# Moteino.net
KiCad netlist of a schematic drawn in EAGLE
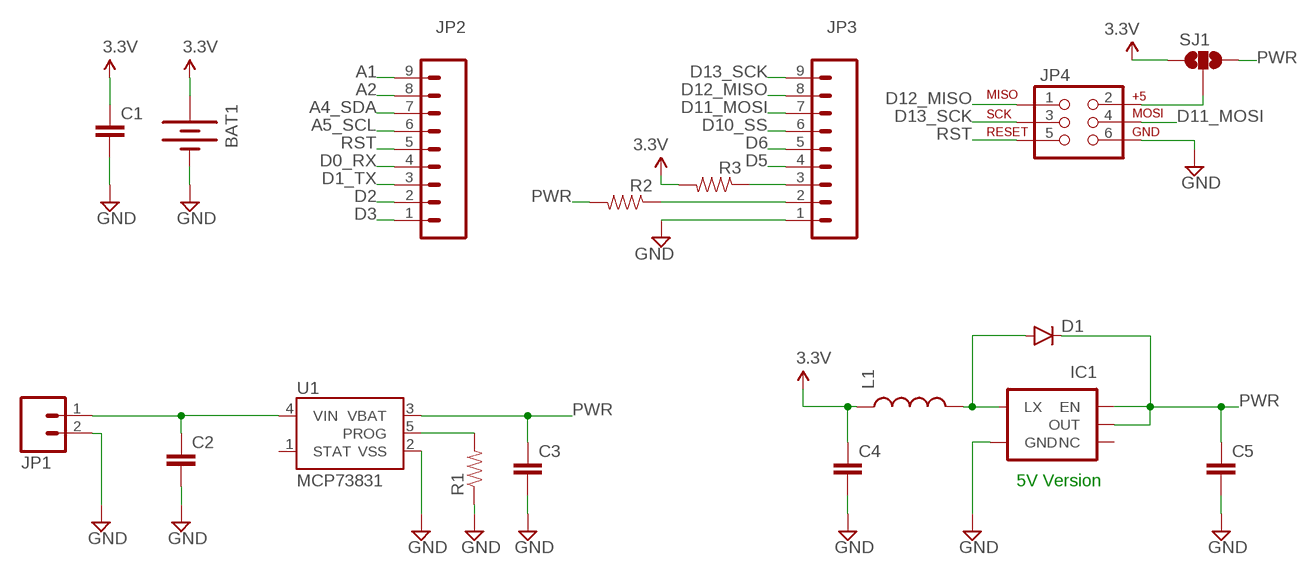
[diagram p0: schematic, sheet 1]

(export (version "E")
  (design (tool "Eeschema 10.0.6"))
  (components
    (comp (ref "BAT1")
      (value "BATTERY12MM")
      (footprint "eagle-import:BATTCON_12MM")
      (libsource (lib "eagle-import") (part "BATTERY12MM"))
    )
    (comp (ref "C1")
      (value "CAP0603-CAP")
      (footprint "eagle-import:0603-CAP")
      (libsource (lib "eagle-import") (part "CAP0603-CAP"))
    )
    (comp (ref "C2")
      (value "CAP0603-CAP")
      (footprint "eagle-import:0603-CAP")
      (libsource (lib "eagle-import") (part "CAP0603-CAP"))
    )
    (comp (ref "C3")
      (value "CAP0603-CAP")
      (footprint "eagle-import:0603-CAP")
      (libsource (lib "eagle-import") (part "CAP0603-CAP"))
    )
    (comp (ref "C4")
      (value "CAP0603-CAP")
      (footprint "eagle-import:0603-CAP")
      (libsource (lib "eagle-import") (part "CAP0603-CAP"))
    )
    (comp (ref "C5")
      (value "CAP0603-CAP")
      (footprint "eagle-import:0603-CAP")
      (libsource (lib "eagle-import") (part "CAP0603-CAP"))
    )
    (comp (ref "D1")
      (value "DIODESMA")
      (footprint "eagle-import:SMA-DIODE")
      (libsource (lib "eagle-import") (part "DIODESMA"))
    )
    (comp (ref "IC1")
      (value "V_REG_NCP1400SOT23-5")
      (footprint "eagle-import:SOT23-5")
      (libsource (lib "eagle-import") (part "V_REG_NCP1400SOT23-5"))
    )
    (comp (ref "JP1")
      (value "M02PTH")
      (footprint "eagle-import:1X02")
      (libsource (lib "eagle-import") (part "M02PTH"))
    )
    (comp (ref "JP2")
      (value "M09")
      (footprint "eagle-import:1X09")
      (libsource (lib "eagle-import") (part "M09"))
    )
    (comp (ref "JP3")
      (value "M09")
      (footprint "eagle-import:1X09")
      (libsource (lib "eagle-import") (part "M09"))
    )
    (comp (ref "JP4")
      (value "AVR_SPI_PRG_6TESTPOINTS")
      (footprint "eagle-import:2X3_TEST_POINTS")
      (libsource (lib "eagle-import") (part "AVR_SPI_PRG_6TESTPOINTS"))
    )
    (comp (ref "L1")
      (value "INDUCTORINDUCTOR_4.7UH")
      (footprint "eagle-import:INDUCTOR_4.7UH")
      (libsource (lib "eagle-import") (part "INDUCTORINDUCTOR_4.7UH"))
    )
    (comp (ref "R1")
      (value "RESISTOR0603-RES")
      (footprint "eagle-import:0603-RES")
      (libsource (lib "eagle-import") (part "RESISTOR0603-RES"))
    )
    (comp (ref "R2")
      (value "RESISTOR0603-RES")
      (footprint "eagle-import:0603-RES")
      (libsource (lib "eagle-import") (part "RESISTOR0603-RES"))
    )
    (comp (ref "R3")
      (value "RESISTOR0603-RES")
      (footprint "eagle-import:0603-RES")
      (libsource (lib "eagle-import") (part "RESISTOR0603-RES"))
    )
    (comp (ref "SJ1")
      (value "JUMPER-PAD-3-NOFULL_BOX_SILK")
      (footprint "eagle-import:PAD-JUMPER-3-NO_YES_SILK_FULL_BOX")
      (libsource (lib "eagle-import") (part "JUMPER-PAD-3-NOFULL_BOX_SILK"))
    )
    (comp (ref "U1")
      (value "MCP73831")
      (footprint "eagle-import:SOT23-5")
      (libsource (lib "eagle-import") (part "MCP73831"))
    )
  )
  (nets
    (net (code "1") (name "/A1") (class "Default")
      (node (ref "JP2") (pin "9") (pinfunction "9_9") (pintype "passive"))
    )
    (net (code "2") (name "/A2") (class "Default")
      (node (ref "JP2") (pin "8") (pinfunction "8_8") (pintype "passive"))
    )
    (net (code "3") (name "/A4_SDA") (class "Default")
      (node (ref "JP2") (pin "7") (pinfunction "7_7") (pintype "passive"))
    )
    (net (code "4") (name "/A5_SCL") (class "Default")
      (node (ref "JP2") (pin "6") (pinfunction "6_6") (pintype "passive"))
    )
    (net (code "5") (name "/D0_RX") (class "Default")
      (node (ref "JP2") (pin "4") (pinfunction "4_4") (pintype "passive"))
    )
    (net (code "6") (name "/D1_TX") (class "Default")
      (node (ref "JP2") (pin "3") (pinfunction "3_3") (pintype "passive"))
    )
    (net (code "7") (name "/D2") (class "Default")
      (node (ref "JP2") (pin "2") (pinfunction "2_2") (pintype "passive"))
    )
    (net (code "8") (name "/D3") (class "Default")
      (node (ref "JP2") (pin "1") (pinfunction "1_1") (pintype "passive"))
    )
    (net (code "9") (name "/D5") (class "Default")
      (node (ref "JP3") (pin "4") (pinfunction "4_4") (pintype "passive"))
    )
    (net (code "10") (name "/D6") (class "Default")
      (node (ref "JP3") (pin "5") (pinfunction "5_5") (pintype "passive"))
    )
    (net (code "11") (name "/D10_SS") (class "Default")
      (node (ref "JP3") (pin "6") (pinfunction "6_6") (pintype "passive"))
    )
    (net (code "12") (name "/D11_MOSI") (class "Default")
      (node (ref "JP3") (pin "7") (pinfunction "7_7") (pintype "passive"))
      (node (ref "JP4") (pin "4") (pinfunction "4_4") (pintype "passive"))
    )
    (net (code "13") (name "/D12_MISO") (class "Default")
      (node (ref "JP3") (pin "8") (pinfunction "8_8") (pintype "passive"))
      (node (ref "JP4") (pin "1") (pinfunction "1_1") (pintype "passive"))
    )
    (net (code "14") (name "/D13_SCK") (class "Default")
      (node (ref "JP3") (pin "9") (pinfunction "9_9") (pintype "passive"))
      (node (ref "JP4") (pin "3") (pinfunction "3_3") (pintype "passive"))
    )
    (net (code "15") (name "/PWR") (class "Default")
      (node (ref "C3") (pin "1") (pinfunction "1_1") (pintype "passive"))
      (node (ref "C5") (pin "1") (pinfunction "1_1") (pintype "passive"))
      (node (ref "D1") (pin "C") (pinfunction "C_C") (pintype "passive"))
      (node (ref "IC1") (pin "1") (pinfunction "EN_1") (pintype "input"))
      (node (ref "IC1") (pin "2") (pinfunction "OUT_2") (pintype "passive"))
      (node (ref "R2") (pin "2") (pinfunction "2_2") (pintype "passive"))
      (node (ref "SJ1") (pin "3") (pinfunction "3_3") (pintype "passive"))
      (node (ref "U1") (pin "3") (pinfunction "VBAT_3") (pintype "power_in"))
    )
    (net (code "16") (name "/RST") (class "Default")
      (node (ref "JP2") (pin "5") (pinfunction "5_5") (pintype "passive"))
      (node (ref "JP4") (pin "5") (pinfunction "5_5") (pintype "passive"))
    )
    (net (code "17") (name "3.3V") (class "Default")
      (node (ref "BAT1") (pin "PWR@1") (pinfunction "+_PWR@1") (pintype "power_in"))
      (node (ref "C1") (pin "1") (pinfunction "1_1") (pintype "passive"))
      (node (ref "C4") (pin "1") (pinfunction "1_1") (pintype "passive"))
      (node (ref "L1") (pin "P$1") (pinfunction "1_P$1") (pintype "passive"))
      (node (ref "R3") (pin "2") (pinfunction "2_2") (pintype "passive"))
      (node (ref "SJ1") (pin "1") (pinfunction "1_1") (pintype "passive"))
    )
    (net (code "18") (name "GND") (class "Default")
      (node (ref "BAT1") (pin "GND") (pinfunction "-_GND") (pintype "power_in"))
      (node (ref "C1") (pin "2") (pinfunction "2_2") (pintype "passive"))
      (node (ref "C2") (pin "2") (pinfunction "2_2") (pintype "passive"))
      (node (ref "C3") (pin "2") (pinfunction "2_2") (pintype "passive"))
      (node (ref "C4") (pin "2") (pinfunction "2_2") (pintype "passive"))
      (node (ref "C5") (pin "2") (pinfunction "2_2") (pintype "passive"))
      (node (ref "IC1") (pin "4") (pinfunction "GND_4") (pintype "input"))
      (node (ref "JP1") (pin "2") (pinfunction "2_2") (pintype "passive"))
      (node (ref "JP3") (pin "1") (pinfunction "1_1") (pintype "passive"))
      (node (ref "JP4") (pin "6") (pinfunction "6_6") (pintype "passive"))
      (node (ref "R1") (pin "1") (pinfunction "1_1") (pintype "passive"))
      (node (ref "U1") (pin "2") (pinfunction "VSS_2") (pintype "power_in"))
    )
    (net (code "19") (name "Net-(JP3-Pad2)") (class "Default")
      (node (ref "JP3") (pin "2") (pinfunction "2_2") (pintype "passive"))
      (node (ref "R2") (pin "1") (pinfunction "1_1") (pintype "passive"))
    )
    (net (code "20") (name "Net-(JP3-Pad3)") (class "Default")
      (node (ref "JP3") (pin "3") (pinfunction "3_3") (pintype "passive"))
      (node (ref "R3") (pin "1") (pinfunction "1_1") (pintype "passive"))
    )
    (net (code "21") (name "Net-(JP4-Pad2)") (class "Default")
      (node (ref "JP4") (pin "2") (pinfunction "2_2") (pintype "passive"))
      (node (ref "SJ1") (pin "2") (pinfunction "2_2") (pintype "passive"))
    )
    (net (code "22") (name "Net-(L1-2)") (class "Default")
      (node (ref "D1") (pin "A") (pinfunction "A_A") (pintype "passive"))
      (node (ref "L1") (pin "P$2") (pinfunction "2_P$2") (pintype "passive"))
    )
    (net (code "23") (name "Net-(U1-PROG)") (class "Default")
      (node (ref "R1") (pin "2") (pinfunction "2_2") (pintype "passive"))
      (node (ref "U1") (pin "5") (pinfunction "PROG_5") (pintype "input"))
    )
    (net (code "24") (name "Net-(U1-VIN)") (class "Default")
      (node (ref "C2") (pin "1") (pinfunction "1_1") (pintype "passive"))
      (node (ref "JP1") (pin "1") (pinfunction "1_1") (pintype "passive"))
      (node (ref "U1") (pin "4") (pinfunction "VIN_4") (pintype "power_in"))
    )
    (net (code "25") (name "unconnected-(IC1-LX-Pad5)") (class "Default")
      (node (ref "IC1") (pin "5") (pinfunction "LX_5") (pintype "input"))
    )
    (net (code "26") (name "unconnected-(IC1-NC-Pad3)") (class "Default")
      (node (ref "IC1") (pin "3") (pinfunction "NC_3") (pintype "input"))
    )
    (net (code "27") (name "unconnected-(U1-STAT-Pad1)") (class "Default")
      (node (ref "U1") (pin "1") (pinfunction "STAT_1") (pintype "output"))
    )
  )
)
